# BG95-SHEEET.net
KiCad netlist of a schematic drawn in Altium Designer
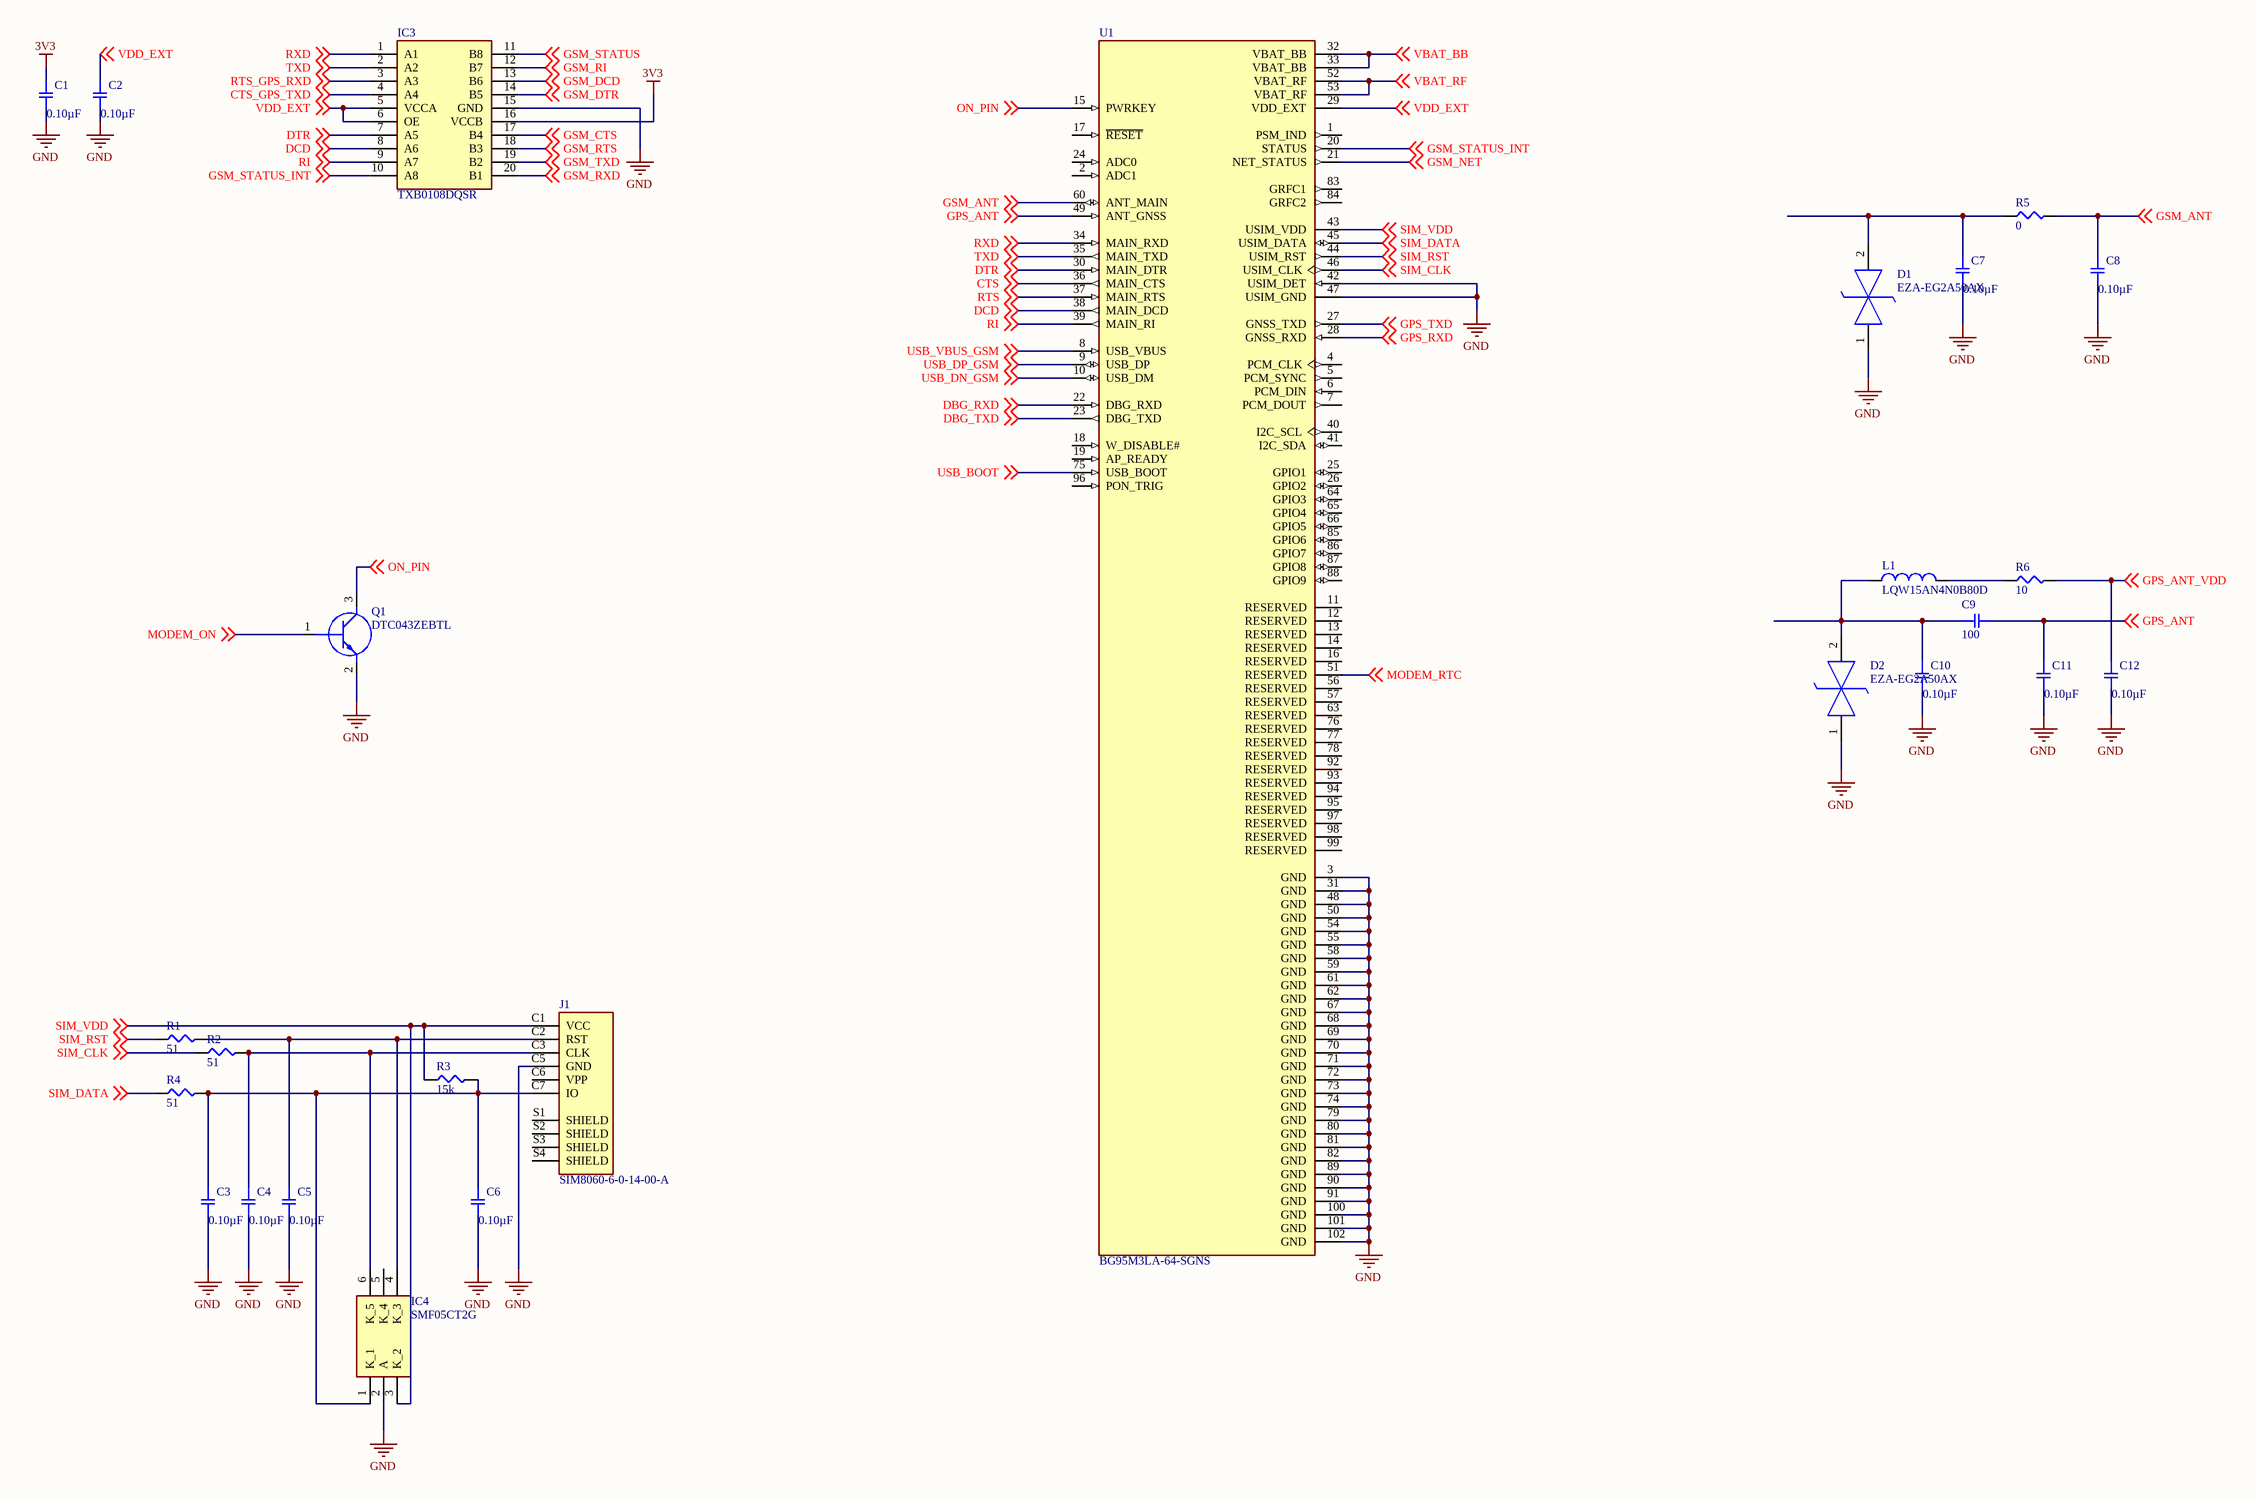
[diagram p0: BG95-SHEEET.SchDoc]

(export (version "E")
  (design (tool "Eeschema 10.0.6"))
  (components
    (comp (ref "C1")
      (value "0.10µF")
      (footprint "SMD-0402C")
      (description "CAP CER 0.1UF 10V X5R 0402")
      (fields
        (field (name "DIGI-KEY PART NUMBER") "490-10008-1-ND")
        (field (name "PART NUMBER") "GRM152R61A104KE19D")
      )
      (libsource (lib "capacitor_murata_0402") (part "GRM152R61A104KE19D"))
    )
    (comp (ref "C2")
      (value "0.10µF")
      (footprint "SMD-0402C")
      (description "CAP CER 0.1UF 10V X5R 0402")
      (fields
        (field (name "DIGI-KEY PART NUMBER") "490-10008-1-ND")
        (field (name "PART NUMBER") "GRM152R61A104KE19D")
      )
      (libsource (lib "capacitor_murata_0402") (part "GRM152R61A104KE19D"))
    )
    (comp (ref "C3")
      (value "0.10µF")
      (footprint "SMD-0402C")
      (description "CAP CER 0.1UF 10V X5R 0402")
      (fields
        (field (name "DIGI-KEY PART NUMBER") "490-10008-1-ND")
        (field (name "PART NUMBER") "GRM152R61A104KE19D")
      )
      (libsource (lib "capacitor_murata_0402") (part "GRM152R61A104KE19D"))
    )
    (comp (ref "C4")
      (value "0.10µF")
      (footprint "SMD-0402C")
      (description "CAP CER 0.1UF 10V X5R 0402")
      (fields
        (field (name "DIGI-KEY PART NUMBER") "490-10008-1-ND")
        (field (name "PART NUMBER") "GRM152R61A104KE19D")
      )
      (libsource (lib "capacitor_murata_0402") (part "GRM152R61A104KE19D"))
    )
    (comp (ref "C5")
      (value "0.10µF")
      (footprint "SMD-0402C")
      (description "CAP CER 0.1UF 10V X5R 0402")
      (fields
        (field (name "DIGI-KEY PART NUMBER") "490-10008-1-ND")
        (field (name "PART NUMBER") "GRM152R61A104KE19D")
      )
      (libsource (lib "capacitor_murata_0402") (part "GRM152R61A104KE19D"))
    )
    (comp (ref "C6")
      (value "0.10µF")
      (footprint "SMD-0402C")
      (description "CAP CER 0.1UF 10V X5R 0402")
      (fields
        (field (name "DIGI-KEY PART NUMBER") "490-10008-1-ND")
        (field (name "PART NUMBER") "GRM152R61A104KE19D")
      )
      (libsource (lib "capacitor_murata_0402") (part "GRM152R61A104KE19D"))
    )
    (comp (ref "C7")
      (value "0.10µF")
      (footprint "SMD-0402C")
      (description "CAP CER 0.1UF 10V X5R 0402")
      (fields
        (field (name "DIGI-KEY PART NUMBER") "490-10008-1-ND")
        (field (name "PART NUMBER") "GRM152R61A104KE19D")
      )
      (libsource (lib "capacitor_murata_0402") (part "GRM152R61A104KE19D"))
    )
    (comp (ref "C8")
      (value "0.10µF")
      (footprint "SMD-0402C")
      (description "CAP CER 0.1UF 10V X5R 0402")
      (fields
        (field (name "DIGI-KEY PART NUMBER") "490-10008-1-ND")
        (field (name "PART NUMBER") "GRM152R61A104KE19D")
      )
      (libsource (lib "capacitor_murata_0402") (part "GRM152R61A104KE19D"))
    )
    (comp (ref "C9")
      (value "100")
      (footprint "SMD-0402C")
      (description "CAP CER 0.1UF 10V X5R 0402")
      (fields
        (field (name "DIGI-KEY PART NUMBER") "490-10008-1-ND")
        (field (name "PART NUMBER") "GRM152R61A104KE19D")
      )
      (libsource (lib "capacitor_murata_0402") (part "GRM152R61A104KE19D"))
    )
    (comp (ref "C10")
      (value "0.10µF")
      (footprint "SMD-0402C")
      (description "CAP CER 0.1UF 10V X5R 0402")
      (fields
        (field (name "DIGI-KEY PART NUMBER") "490-10008-1-ND")
        (field (name "PART NUMBER") "GRM152R61A104KE19D")
      )
      (libsource (lib "capacitor_murata_0402") (part "GRM152R61A104KE19D"))
    )
    (comp (ref "C11")
      (value "0.10µF")
      (footprint "SMD-0402C")
      (description "CAP CER 0.1UF 10V X5R 0402")
      (fields
        (field (name "DIGI-KEY PART NUMBER") "490-10008-1-ND")
        (field (name "PART NUMBER") "GRM152R61A104KE19D")
      )
      (libsource (lib "capacitor_murata_0402") (part "GRM152R61A104KE19D"))
    )
    (comp (ref "C12")
      (value "0.10µF")
      (footprint "SMD-0402C")
      (description "CAP CER 0.1UF 10V X5R 0402")
      (fields
        (field (name "DIGI-KEY PART NUMBER") "490-10008-1-ND")
        (field (name "PART NUMBER") "GRM152R61A104KE19D")
      )
      (libsource (lib "capacitor_murata_0402") (part "GRM152R61A104KE19D"))
    )
    (comp (ref "D1")
      (value "EZA-EG2A50AX")
      (footprint "SamacSys:EZAEG2A50AX")
      (description "Diode ESD (Bi-directional)")
      (fields (field (name "MOUSER PART NUMBER") "667-EZA-EG2A50AX"))
      (libsource (lib "*") (part "EZA-EG2A50AX"))
    )
    (comp (ref "D2")
      (value "EZA-EG2A50AX")
      (footprint "SamacSys:EZAEG2A50AX")
      (description "Diode ESD (Bi-directional)")
      (fields (field (name "MOUSER PART NUMBER") "667-EZA-EG2A50AX"))
      (libsource (lib "*") (part "EZA-EG2A50AX"))
    )
    (comp (ref "IC3")
      (value "TXB0108DQSR")
      (footprint "SamacSys:TXB0108DQSR")
      (description "Integrated Circuit")
      (fields (field (name "MOUSER PART NUMBER") "595-TXB0108DQSR"))
      (libsource (lib "*") (part "TXB0108DQSR"))
    )
    (comp (ref "IC4")
      (value "SMF05CT2G")
      (footprint "SamacSys:SOT65P210X110-6N")
      (description "Integrated Circuit")
      (fields (field (name "MOUSER PART NUMBER") "863-SMF05CT2G"))
      (libsource (lib "*") (part "SMF05CT2G"))
    )
    (comp (ref "J1")
      (value "SIM8060-6-0-14-00-A")
      (footprint "SIM8060-6-0-14-00-A:GCT_SIM8060-6-0-14-00-A")
      (fields (field (name "MF") "{'manufacturer': u'Global Connector Technology'}"))
      (libsource (lib "*") (part "SIM8060-6-0-14-00-A"))
    )
    (comp (ref "L1")
      (value "LQW15AN4N0B80D")
      (footprint "LQW15AN4N0B80D:INDC1006X60N")
      (description "Ind RF Chip Unshielded Wirewound 4nH 0.1nH 100MHz 30Q-Factor 1950mA 0402 Paper T/R")
      (fields (field (name "MF") "{'manufacturer': u'Murata'}"))
      (libsource (lib "*") (part "LQW15AN4N0B80D"))
    )
    (comp (ref "Q1")
      (value "DTC043ZEBTL")
      (footprint "SamacSys:SOTFL50P160X85-3N")
      (description "Transistor BJT NPN")
      (fields (field (name "MOUSER PART NUMBER") "755-DTC043ZEBTL"))
      (libsource (lib "*") (part "DTC043ZEBTL"))
    )
    (comp (ref "R1")
      (value "51")
      (footprint "SMD-0402-RES")
      (description "RES SMD 51 OHM 5% 1/10W 0402")
      (fields (field (name "PART NUMBER") "ERJ-2GEJ510X") (field (name "DIGI-KEY PART NUMBER") "P51JCT-ND"))
      (libsource (lib "Panasonic_ERJ_0402") (part "ERJ-2GEJ510X"))
    )
    (comp (ref "R2")
      (value "51")
      (footprint "SMD-0402-RES")
      (description "RES SMD 51 OHM 5% 1/10W 0402")
      (fields (field (name "PART NUMBER") "ERJ-2GEJ510X") (field (name "DIGI-KEY PART NUMBER") "P51JCT-ND"))
      (libsource (lib "Panasonic_ERJ_0402") (part "ERJ-2GEJ510X"))
    )
    (comp (ref "R3")
      (value "15k")
      (footprint "SMD-0402-RES")
      (description "RES SMD 15K OHM 5% 1/10W 0402")
      (fields (field (name "PART NUMBER") "ERJ-2GEJ153X") (field (name "DIGI-KEY PART NUMBER") "P15KJCT-ND"))
      (libsource (lib "Panasonic_ERJ_0402") (part "ERJ-2GEJ153X"))
    )
    (comp (ref "R4")
      (value "51")
      (footprint "SMD-0402-RES")
      (description "RES SMD 51 OHM 5% 1/10W 0402")
      (fields (field (name "PART NUMBER") "ERJ-2GEJ510X") (field (name "DIGI-KEY PART NUMBER") "P51JCT-ND"))
      (libsource (lib "Panasonic_ERJ_0402") (part "ERJ-2GEJ510X"))
    )
    (comp (ref "R5")
      (value "0")
      (footprint "SMD-0402-RES")
      (description "RES SMD 10 OHM 5% 1/10W 0402")
      (fields (field (name "PART NUMBER") "ERJ-2GEJ100X") (field (name "DIGI-KEY PART NUMBER") "P10JCT-ND"))
      (libsource (lib "Panasonic_ERJ_0402") (part "ERJ-2GEJ100X"))
    )
    (comp (ref "R6")
      (value "10")
      (footprint "SMD-0402-RES")
      (description "RES SMD 10 OHM 5% 1/10W 0402")
      (fields (field (name "PART NUMBER") "ERJ-2GEJ100X") (field (name "DIGI-KEY PART NUMBER") "P10JCT-ND"))
      (libsource (lib "Panasonic_ERJ_0402") (part "ERJ-2GEJ100X"))
    )
    (comp (ref "U1")
      (value "BG95M3LA-64-SGNS")
      (footprint "BG95M3LA-64-SGNS:XCVR_BG95M3LA-64-SGNS")
      (fields (field (name "MF") "{'manufacturer': u'Quectel Wireless Solutions Co., Ltd'}"))
      (libsource (lib "*") (part "BG95M3LA-64-SGNS"))
    )
  )
  (nets
    (net (code "1") (name "3V3") (class "Default")
      (node (ref "C1") (pin "1") (pinfunction "1_1") (pintype "passive"))
      (node (ref "IC3") (pin "16") (pinfunction "VCCB_16") (pintype "passive"))
    )
    (net (code "2") (name "CTS") (class "Default")
      (node (ref "U1") (pin "36") (pinfunction "MAIN_CTS_36") (pintype "output"))
    )
    (net (code "3") (name "CTS_GPS_TXD") (class "Default")
      (node (ref "IC3") (pin "4") (pinfunction "A4_4") (pintype "passive"))
    )
    (net (code "4") (name "DBG_RXD") (class "Default")
      (node (ref "U1") (pin "22") (pinfunction "DBG_RXD_22") (pintype "input"))
    )
    (net (code "5") (name "DBG_TXD") (class "Default")
      (node (ref "U1") (pin "23") (pinfunction "DBG_TXD_23") (pintype "output"))
    )
    (net (code "6") (name "DCD") (class "Default")
      (node (ref "IC3") (pin "8") (pinfunction "A6_8") (pintype "passive"))
      (node (ref "U1") (pin "38") (pinfunction "MAIN_DCD_38") (pintype "output"))
    )
    (net (code "7") (name "DTR") (class "Default")
      (node (ref "IC3") (pin "7") (pinfunction "A5_7") (pintype "passive"))
      (node (ref "U1") (pin "30") (pinfunction "MAIN_DTR_30") (pintype "input"))
    )
    (net (code "8") (name "GND") (class "Default")
      (node (ref "C1") (pin "2") (pinfunction "2_2") (pintype "passive"))
      (node (ref "C10") (pin "2") (pinfunction "2_2") (pintype "passive"))
      (node (ref "C11") (pin "2") (pinfunction "2_2") (pintype "passive"))
      (node (ref "C12") (pin "2") (pinfunction "2_2") (pintype "passive"))
      (node (ref "C2") (pin "2") (pinfunction "2_2") (pintype "passive"))
      (node (ref "C3") (pin "2") (pinfunction "2_2") (pintype "passive"))
      (node (ref "C4") (pin "2") (pinfunction "2_2") (pintype "passive"))
      (node (ref "C5") (pin "2") (pinfunction "2_2") (pintype "passive"))
      (node (ref "C6") (pin "2") (pinfunction "2_2") (pintype "passive"))
      (node (ref "C7") (pin "2") (pinfunction "2_2") (pintype "passive"))
      (node (ref "C8") (pin "2") (pinfunction "2_2") (pintype "passive"))
      (node (ref "D1") (pin "1") (pinfunction "K1_1") (pintype "passive"))
      (node (ref "D2") (pin "1") (pinfunction "K1_1") (pintype "passive"))
      (node (ref "IC3") (pin "15") (pinfunction "GND_15") (pintype "passive"))
      (node (ref "IC4") (pin "2") (pinfunction "A_2") (pintype "passive"))
      (node (ref "J1") (pin "C5") (pinfunction "GND_C5") (pintype "passive"))
      (node (ref "Q1") (pin "2") (pinfunction "E_2") (pintype "passive"))
      (node (ref "U1") (pin "100") (pinfunction "GND_100") (pintype "power_in"))
      (node (ref "U1") (pin "101") (pinfunction "GND_101") (pintype "power_in"))
      (node (ref "U1") (pin "102") (pinfunction "GND_102") (pintype "power_in"))
      (node (ref "U1") (pin "3") (pinfunction "GND_3") (pintype "power_in"))
      (node (ref "U1") (pin "31") (pinfunction "GND_31") (pintype "power_in"))
      (node (ref "U1") (pin "42") (pinfunction "USIM_DET_42") (pintype "input"))
      (node (ref "U1") (pin "47") (pinfunction "USIM_GND_47") (pintype "power_in"))
      (node (ref "U1") (pin "48") (pinfunction "GND_48") (pintype "power_in"))
      (node (ref "U1") (pin "50") (pinfunction "GND_50") (pintype "power_in"))
      (node (ref "U1") (pin "54") (pinfunction "GND_54") (pintype "power_in"))
      (node (ref "U1") (pin "55") (pinfunction "GND_55") (pintype "power_in"))
      (node (ref "U1") (pin "58") (pinfunction "GND_58") (pintype "power_in"))
      (node (ref "U1") (pin "59") (pinfunction "GND_59") (pintype "power_in"))
      (node (ref "U1") (pin "61") (pinfunction "GND_61") (pintype "power_in"))
      (node (ref "U1") (pin "62") (pinfunction "GND_62") (pintype "power_in"))
      (node (ref "U1") (pin "67") (pinfunction "GND_67") (pintype "power_in"))
      (node (ref "U1") (pin "68") (pinfunction "GND_68") (pintype "power_in"))
      (node (ref "U1") (pin "69") (pinfunction "GND_69") (pintype "power_in"))
      (node (ref "U1") (pin "70") (pinfunction "GND_70") (pintype "power_in"))
      (node (ref "U1") (pin "71") (pinfunction "GND_71") (pintype "power_in"))
      (node (ref "U1") (pin "72") (pinfunction "GND_72") (pintype "power_in"))
      (node (ref "U1") (pin "73") (pinfunction "GND_73") (pintype "power_in"))
      (node (ref "U1") (pin "74") (pinfunction "GND_74") (pintype "power_in"))
      (node (ref "U1") (pin "79") (pinfunction "GND_79") (pintype "power_in"))
      (node (ref "U1") (pin "80") (pinfunction "GND_80") (pintype "power_in"))
      (node (ref "U1") (pin "81") (pinfunction "GND_81") (pintype "power_in"))
      (node (ref "U1") (pin "82") (pinfunction "GND_82") (pintype "power_in"))
      (node (ref "U1") (pin "89") (pinfunction "GND_89") (pintype "power_in"))
      (node (ref "U1") (pin "90") (pinfunction "GND_90") (pintype "power_in"))
      (node (ref "U1") (pin "91") (pinfunction "GND_91") (pintype "power_in"))
    )
    (net (code "9") (name "GPS_ANT") (class "Default")
      (node (ref "C11") (pin "1") (pinfunction "1_1") (pintype "passive"))
      (node (ref "C9") (pin "2") (pinfunction "2_2") (pintype "passive"))
      (node (ref "U1") (pin "49") (pinfunction "ANT_GNSS_49") (pintype "input"))
    )
    (net (code "10") (name "GPS_ANT_VDD") (class "Default")
      (node (ref "C12") (pin "1") (pinfunction "1_1") (pintype "passive"))
      (node (ref "R6") (pin "2") (pinfunction "2_2") (pintype "passive"))
    )
    (net (code "11") (name "GPS_RXD") (class "Default")
      (node (ref "U1") (pin "28") (pinfunction "GNSS_RXD_28") (pintype "input"))
    )
    (net (code "12") (name "GPS_TXD") (class "Default")
      (node (ref "U1") (pin "27") (pinfunction "GNSS_TXD_27") (pintype "output"))
    )
    (net (code "13") (name "GSM_ANT") (class "Default")
      (node (ref "C8") (pin "1") (pinfunction "1_1") (pintype "passive"))
      (node (ref "R5") (pin "2") (pinfunction "2_2") (pintype "passive"))
      (node (ref "U1") (pin "60") (pinfunction "ANT_MAIN_60") (pintype "bidirectional"))
    )
    (net (code "14") (name "GSM_CTS") (class "Default")
      (node (ref "IC3") (pin "17") (pinfunction "B4_17") (pintype "passive"))
    )
    (net (code "15") (name "GSM_DCD") (class "Default")
      (node (ref "IC3") (pin "13") (pinfunction "B6_13") (pintype "passive"))
    )
    (net (code "16") (name "GSM_DTR") (class "Default")
      (node (ref "IC3") (pin "14") (pinfunction "B5_14") (pintype "passive"))
    )
    (net (code "17") (name "GSM_NET") (class "Default")
      (node (ref "U1") (pin "21") (pinfunction "NET_STATUS_21") (pintype "output"))
    )
    (net (code "18") (name "GSM_RI") (class "Default")
      (node (ref "IC3") (pin "12") (pinfunction "B7_12") (pintype "passive"))
    )
    (net (code "19") (name "GSM_RTS") (class "Default")
      (node (ref "IC3") (pin "18") (pinfunction "B3_18") (pintype "passive"))
    )
    (net (code "20") (name "GSM_RXD") (class "Default")
      (node (ref "IC3") (pin "20") (pinfunction "B1_20") (pintype "passive"))
    )
    (net (code "21") (name "GSM_STATUS") (class "Default")
      (node (ref "IC3") (pin "11") (pinfunction "B8_11") (pintype "passive"))
    )
    (net (code "22") (name "GSM_STATUS_INT") (class "Default")
      (node (ref "IC3") (pin "10") (pinfunction "A8_10") (pintype "passive"))
      (node (ref "U1") (pin "20") (pinfunction "STATUS_20") (pintype "output"))
    )
    (net (code "23") (name "GSM_TXD") (class "Default")
      (node (ref "IC3") (pin "19") (pinfunction "B2_19") (pintype "passive"))
    )
    (net (code "24") (name "MODEM_ON") (class "Default")
      (node (ref "Q1") (pin "1") (pinfunction "B_1") (pintype "passive"))
    )
    (net (code "25") (name "MODEM_RTC") (class "Default")
      (node (ref "U1") (pin "51") (pinfunction "RESERVED_51") (pintype "passive"))
    )
    (net (code "26") (name "Net-(D1-K2)") (class "Default")
      (node (ref "C7") (pin "1") (pinfunction "1_1") (pintype "passive"))
      (node (ref "D1") (pin "2") (pinfunction "K2_2") (pintype "passive"))
      (node (ref "R5") (pin "1") (pinfunction "1_1") (pintype "passive"))
    )
    (net (code "27") (name "Net-(D2-K2)") (class "Default")
      (node (ref "C10") (pin "1") (pinfunction "1_1") (pintype "passive"))
      (node (ref "C9") (pin "1") (pinfunction "1_1") (pintype "passive"))
      (node (ref "D2") (pin "2") (pinfunction "K2_2") (pintype "passive"))
      (node (ref "L1") (pin "1") (pinfunction "1_1") (pintype "passive"))
    )
    (net (code "28") (name "Net-(IC4-K_1)") (class "Default")
      (node (ref "C3") (pin "1") (pinfunction "1_1") (pintype "passive"))
      (node (ref "C6") (pin "1") (pinfunction "1_1") (pintype "passive"))
      (node (ref "IC4") (pin "1") (pinfunction "K_1_1") (pintype "passive"))
      (node (ref "J1") (pin "C7") (pinfunction "IO_C7") (pintype "passive"))
      (node (ref "R3") (pin "2") (pinfunction "2_2") (pintype "passive"))
      (node (ref "R4") (pin "2") (pinfunction "2_2") (pintype "passive"))
    )
    (net (code "29") (name "Net-(IC4-K_3)") (class "Default")
      (node (ref "C5") (pin "1") (pinfunction "1_1") (pintype "passive"))
      (node (ref "IC4") (pin "4") (pinfunction "K_3_4") (pintype "passive"))
      (node (ref "J1") (pin "C2") (pinfunction "RST_C2") (pintype "passive"))
      (node (ref "R1") (pin "2") (pinfunction "2_2") (pintype "passive"))
    )
    (net (code "30") (name "Net-(IC4-K_5)") (class "Default")
      (node (ref "C4") (pin "1") (pinfunction "1_1") (pintype "passive"))
      (node (ref "IC4") (pin "6") (pinfunction "K_5_6") (pintype "passive"))
      (node (ref "J1") (pin "C3") (pinfunction "CLK_C3") (pintype "passive"))
      (node (ref "R2") (pin "2") (pinfunction "2_2") (pintype "passive"))
    )
    (net (code "31") (name "Net-(L1-Pad2)") (class "Default")
      (node (ref "L1") (pin "2") (pinfunction "2_2") (pintype "passive"))
      (node (ref "R6") (pin "1") (pinfunction "1_1") (pintype "passive"))
    )
    (net (code "32") (name "ON_PIN") (class "Default")
      (node (ref "Q1") (pin "3") (pinfunction "C_3") (pintype "passive"))
      (node (ref "U1") (pin "15") (pinfunction "PWRKEY_15") (pintype "input"))
    )
    (net (code "33") (name "RI") (class "Default")
      (node (ref "IC3") (pin "9") (pinfunction "A7_9") (pintype "passive"))
      (node (ref "U1") (pin "39") (pinfunction "MAIN_RI_39") (pintype "output"))
    )
    (net (code "34") (name "RTS") (class "Default")
      (node (ref "U1") (pin "37") (pinfunction "MAIN_RTS_37") (pintype "input"))
    )
    (net (code "35") (name "RTS_GPS_RXD") (class "Default")
      (node (ref "IC3") (pin "3") (pinfunction "A3_3") (pintype "passive"))
    )
    (net (code "36") (name "RXD") (class "Default")
      (node (ref "IC3") (pin "1") (pinfunction "A1_1") (pintype "passive"))
      (node (ref "U1") (pin "34") (pinfunction "MAIN_RXD_34") (pintype "input"))
    )
    (net (code "37") (name "SIM_CLK") (class "Default")
      (node (ref "R2") (pin "1") (pinfunction "1_1") (pintype "passive"))
      (node (ref "U1") (pin "46") (pinfunction "USIM_CLK_46") (pintype "output"))
    )
    (net (code "38") (name "SIM_DATA") (class "Default")
      (node (ref "R4") (pin "1") (pinfunction "1_1") (pintype "passive"))
      (node (ref "U1") (pin "45") (pinfunction "USIM_DATA_45") (pintype "bidirectional"))
    )
    (net (code "39") (name "SIM_RST") (class "Default")
      (node (ref "R1") (pin "1") (pinfunction "1_1") (pintype "passive"))
      (node (ref "U1") (pin "44") (pinfunction "USIM_RST_44") (pintype "output"))
    )
    (net (code "40") (name "SIM_VDD") (class "Default")
      (node (ref "IC4") (pin "3") (pinfunction "K_2_3") (pintype "passive"))
      (node (ref "J1") (pin "C1") (pinfunction "VCC_C1") (pintype "passive"))
      (node (ref "R3") (pin "1") (pinfunction "1_1") (pintype "passive"))
      (node (ref "U1") (pin "43") (pinfunction "USIM_VDD_43") (pintype "power_in"))
    )
    (net (code "41") (name "TXD") (class "Default")
      (node (ref "IC3") (pin "2") (pinfunction "A2_2") (pintype "passive"))
      (node (ref "U1") (pin "35") (pinfunction "MAIN_TXD_35") (pintype "output"))
    )
    (net (code "42") (name "USB_BOOT") (class "Default")
      (node (ref "U1") (pin "75") (pinfunction "USB_BOOT_75") (pintype "input"))
    )
    (net (code "43") (name "USB_DN_GSM") (class "Default")
      (node (ref "U1") (pin "10") (pinfunction "USB_DM_10") (pintype "bidirectional"))
    )
    (net (code "44") (name "USB_DP_GSM") (class "Default")
      (node (ref "U1") (pin "9") (pinfunction "USB_DP_9") (pintype "bidirectional"))
    )
    (net (code "45") (name "USB_VBUS_GSM") (class "Default")
      (node (ref "U1") (pin "8") (pinfunction "USB_VBUS_8") (pintype "input"))
    )
    (net (code "46") (name "VBAT_BB") (class "Default")
      (node (ref "U1") (pin "32") (pinfunction "VBAT_BB_32") (pintype "power_in"))
      (node (ref "U1") (pin "33") (pinfunction "VBAT_BB_33") (pintype "power_in"))
    )
    (net (code "47") (name "VBAT_RF") (class "Default")
      (node (ref "U1") (pin "52") (pinfunction "VBAT_RF_52") (pintype "power_in"))
      (node (ref "U1") (pin "53") (pinfunction "VBAT_RF_53") (pintype "power_in"))
    )
    (net (code "48") (name "VDD_EXT") (class "Default")
      (node (ref "C2") (pin "1") (pinfunction "1_1") (pintype "passive"))
      (node (ref "IC3") (pin "5") (pinfunction "VCCA_5") (pintype "passive"))
      (node (ref "IC3") (pin "6") (pinfunction "OE_6") (pintype "passive"))
      (node (ref "U1") (pin "29") (pinfunction "VDD_EXT_29") (pintype "power_in"))
    )
    (net (code "49") (name "unconnected-(IC4-K_4-Pad5)") (class "Default")
      (node (ref "IC4") (pin "5") (pinfunction "K_4_5") (pintype "passive"))
    )
    (net (code "50") (name "unconnected-(J1-SHIELD-PadS1)") (class "Default")
      (node (ref "J1") (pin "S1") (pinfunction "SHIELD_S1") (pintype "passive"))
    )
    (net (code "51") (name "unconnected-(J1-SHIELD-PadS2)") (class "Default")
      (node (ref "J1") (pin "S2") (pinfunction "SHIELD_S2") (pintype "passive"))
    )
    (net (code "52") (name "unconnected-(J1-SHIELD-PadS3)") (class "Default")
      (node (ref "J1") (pin "S3") (pinfunction "SHIELD_S3") (pintype "passive"))
    )
    (net (code "53") (name "unconnected-(J1-SHIELD-PadS4)") (class "Default")
      (node (ref "J1") (pin "S4") (pinfunction "SHIELD_S4") (pintype "passive"))
    )
    (net (code "54") (name "unconnected-(J1-VPP-PadC6)") (class "Default")
      (node (ref "J1") (pin "C6") (pinfunction "VPP_C6") (pintype "passive"))
    )
    (net (code "55") (name "unconnected-(U1-ADC0-Pad24)") (class "Default")
      (node (ref "U1") (pin "24") (pinfunction "ADC0_24") (pintype "input"))
    )
    (net (code "56") (name "unconnected-(U1-ADC1-Pad2)") (class "Default")
      (node (ref "U1") (pin "2") (pinfunction "ADC1_2") (pintype "input"))
    )
    (net (code "57") (name "unconnected-(U1-AP_READY-Pad19)") (class "Default")
      (node (ref "U1") (pin "19") (pinfunction "AP_READY_19") (pintype "input"))
    )
    (net (code "58") (name "unconnected-(U1-GPIO1-Pad25)") (class "Default")
      (node (ref "U1") (pin "25") (pinfunction "GPIO1_25") (pintype "bidirectional"))
    )
    (net (code "59") (name "unconnected-(U1-GPIO2-Pad26)") (class "Default")
      (node (ref "U1") (pin "26") (pinfunction "GPIO2_26") (pintype "bidirectional"))
    )
    (net (code "60") (name "unconnected-(U1-GPIO3-Pad64)") (class "Default")
      (node (ref "U1") (pin "64") (pinfunction "GPIO3_64") (pintype "bidirectional"))
    )
    (net (code "61") (name "unconnected-(U1-GPIO4-Pad65)") (class "Default")
      (node (ref "U1") (pin "65") (pinfunction "GPIO4_65") (pintype "bidirectional"))
    )
    (net (code "62") (name "unconnected-(U1-GPIO5-Pad66)") (class "Default")
      (node (ref "U1") (pin "66") (pinfunction "GPIO5_66") (pintype "bidirectional"))
    )
    (net (code "63") (name "unconnected-(U1-GPIO6-Pad85)") (class "Default")
      (node (ref "U1") (pin "85") (pinfunction "GPIO6_85") (pintype "bidirectional"))
    )
    (net (code "64") (name "unconnected-(U1-GPIO7-Pad86)") (class "Default")
      (node (ref "U1") (pin "86") (pinfunction "GPIO7_86") (pintype "bidirectional"))
    )
    (net (code "65") (name "unconnected-(U1-GPIO8-Pad87)") (class "Default")
      (node (ref "U1") (pin "87") (pinfunction "GPIO8_87") (pintype "bidirectional"))
    )
    (net (code "66") (name "unconnected-(U1-GPIO9-Pad88)") (class "Default")
      (node (ref "U1") (pin "88") (pinfunction "GPIO9_88") (pintype "bidirectional"))
    )
    (net (code "67") (name "unconnected-(U1-GRFC1-Pad83)") (class "Default")
      (node (ref "U1") (pin "83") (pinfunction "GRFC1_83") (pintype "output"))
    )
    (net (code "68") (name "unconnected-(U1-GRFC2-Pad84)") (class "Default")
      (node (ref "U1") (pin "84") (pinfunction "GRFC2_84") (pintype "output"))
    )
    (net (code "69") (name "unconnected-(U1-I2C_SCL-Pad40)") (class "Default")
      (node (ref "U1") (pin "40") (pinfunction "I2C_SCL_40") (pintype "output"))
    )
    (net (code "70") (name "unconnected-(U1-I2C_SDA-Pad41)") (class "Default")
      (node (ref "U1") (pin "41") (pinfunction "I2C_SDA_41") (pintype "bidirectional"))
    )
    (net (code "71") (name "unconnected-(U1-PCM_CLK-Pad4)") (class "Default")
      (node (ref "U1") (pin "4") (pinfunction "PCM_CLK_4") (pintype "output"))
    )
    (net (code "72") (name "unconnected-(U1-PCM_DIN-Pad6)") (class "Default")
      (node (ref "U1") (pin "6") (pinfunction "PCM_DIN_6") (pintype "input"))
    )
    (net (code "73") (name "unconnected-(U1-PCM_DOUT-Pad7)") (class "Default")
      (node (ref "U1") (pin "7") (pinfunction "PCM_DOUT_7") (pintype "output"))
    )
    (net (code "74") (name "unconnected-(U1-PCM_SYNC-Pad5)") (class "Default")
      (node (ref "U1") (pin "5") (pinfunction "PCM_SYNC_5") (pintype "output"))
    )
    (net (code "75") (name "unconnected-(U1-PON_TRIG-Pad96)") (class "Default")
      (node (ref "U1") (pin "96") (pinfunction "PON_TRIG_96") (pintype "input"))
    )
    (net (code "76") (name "unconnected-(U1-PSM_IND-Pad1)") (class "Default")
      (node (ref "U1") (pin "1") (pinfunction "PSM_IND_1") (pintype "output"))
    )
    (net (code "77") (name "unconnected-(U1-RESERVED-Pad11)") (class "Default")
      (node (ref "U1") (pin "11") (pinfunction "RESERVED_11") (pintype "passive"))
    )
    (net (code "78") (name "unconnected-(U1-RESERVED-Pad12)") (class "Default")
      (node (ref "U1") (pin "12") (pinfunction "RESERVED_12") (pintype "passive"))
    )
    (net (code "79") (name "unconnected-(U1-RESERVED-Pad13)") (class "Default")
      (node (ref "U1") (pin "13") (pinfunction "RESERVED_13") (pintype "passive"))
    )
    (net (code "80") (name "unconnected-(U1-RESERVED-Pad14)") (class "Default")
      (node (ref "U1") (pin "14") (pinfunction "RESERVED_14") (pintype "passive"))
    )
    (net (code "81") (name "unconnected-(U1-RESERVED-Pad16)") (class "Default")
      (node (ref "U1") (pin "16") (pinfunction "RESERVED_16") (pintype "passive"))
    )
    (net (code "82") (name "unconnected-(U1-RESERVED-Pad56)") (class "Default")
      (node (ref "U1") (pin "56") (pinfunction "RESERVED_56") (pintype "passive"))
    )
    (net (code "83") (name "unconnected-(U1-RESERVED-Pad57)") (class "Default")
      (node (ref "U1") (pin "57") (pinfunction "RESERVED_57") (pintype "passive"))
    )
    (net (code "84") (name "unconnected-(U1-RESERVED-Pad63)") (class "Default")
      (node (ref "U1") (pin "63") (pinfunction "RESERVED_63") (pintype "passive"))
    )
    (net (code "85") (name "unconnected-(U1-RESERVED-Pad76)") (class "Default")
      (node (ref "U1") (pin "76") (pinfunction "RESERVED_76") (pintype "passive"))
    )
    (net (code "86") (name "unconnected-(U1-RESERVED-Pad77)") (class "Default")
      (node (ref "U1") (pin "77") (pinfunction "RESERVED_77") (pintype "passive"))
    )
    (net (code "87") (name "unconnected-(U1-RESERVED-Pad78)") (class "Default")
      (node (ref "U1") (pin "78") (pinfunction "RESERVED_78") (pintype "passive"))
    )
    (net (code "88") (name "unconnected-(U1-RESERVED-Pad92)") (class "Default")
      (node (ref "U1") (pin "92") (pinfunction "RESERVED_92") (pintype "passive"))
    )
    (net (code "89") (name "unconnected-(U1-RESERVED-Pad93)") (class "Default")
      (node (ref "U1") (pin "93") (pinfunction "RESERVED_93") (pintype "passive"))
    )
    (net (code "90") (name "unconnected-(U1-RESERVED-Pad94)") (class "Default")
      (node (ref "U1") (pin "94") (pinfunction "RESERVED_94") (pintype "passive"))
    )
    (net (code "91") (name "unconnected-(U1-RESERVED-Pad95)") (class "Default")
      (node (ref "U1") (pin "95") (pinfunction "RESERVED_95") (pintype "passive"))
    )
    (net (code "92") (name "unconnected-(U1-RESERVED-Pad97)") (class "Default")
      (node (ref "U1") (pin "97") (pinfunction "RESERVED_97") (pintype "passive"))
    )
    (net (code "93") (name "unconnected-(U1-RESERVED-Pad98)") (class "Default")
      (node (ref "U1") (pin "98") (pinfunction "RESERVED_98") (pintype "passive"))
    )
    (net (code "94") (name "unconnected-(U1-RESERVED-Pad99)") (class "Default")
      (node (ref "U1") (pin "99") (pinfunction "RESERVED_99") (pintype "passive"))
    )
    (net (code "95") (name "unconnected-(U1-W_DISABLE#-Pad18)") (class "Default")
      (node (ref "U1") (pin "18") (pinfunction "W_DISABLE#_18") (pintype "input"))
    )
    (net (code "96") (name "unconnected-(U1-~{RESET}-Pad17)") (class "Default")
      (node (ref "U1") (pin "17") (pinfunction "~{RESET}_17") (pintype "input"))
    )
  )
)
